# schematic.net
KiCad netlist of a schematic drawn in EasyEDA
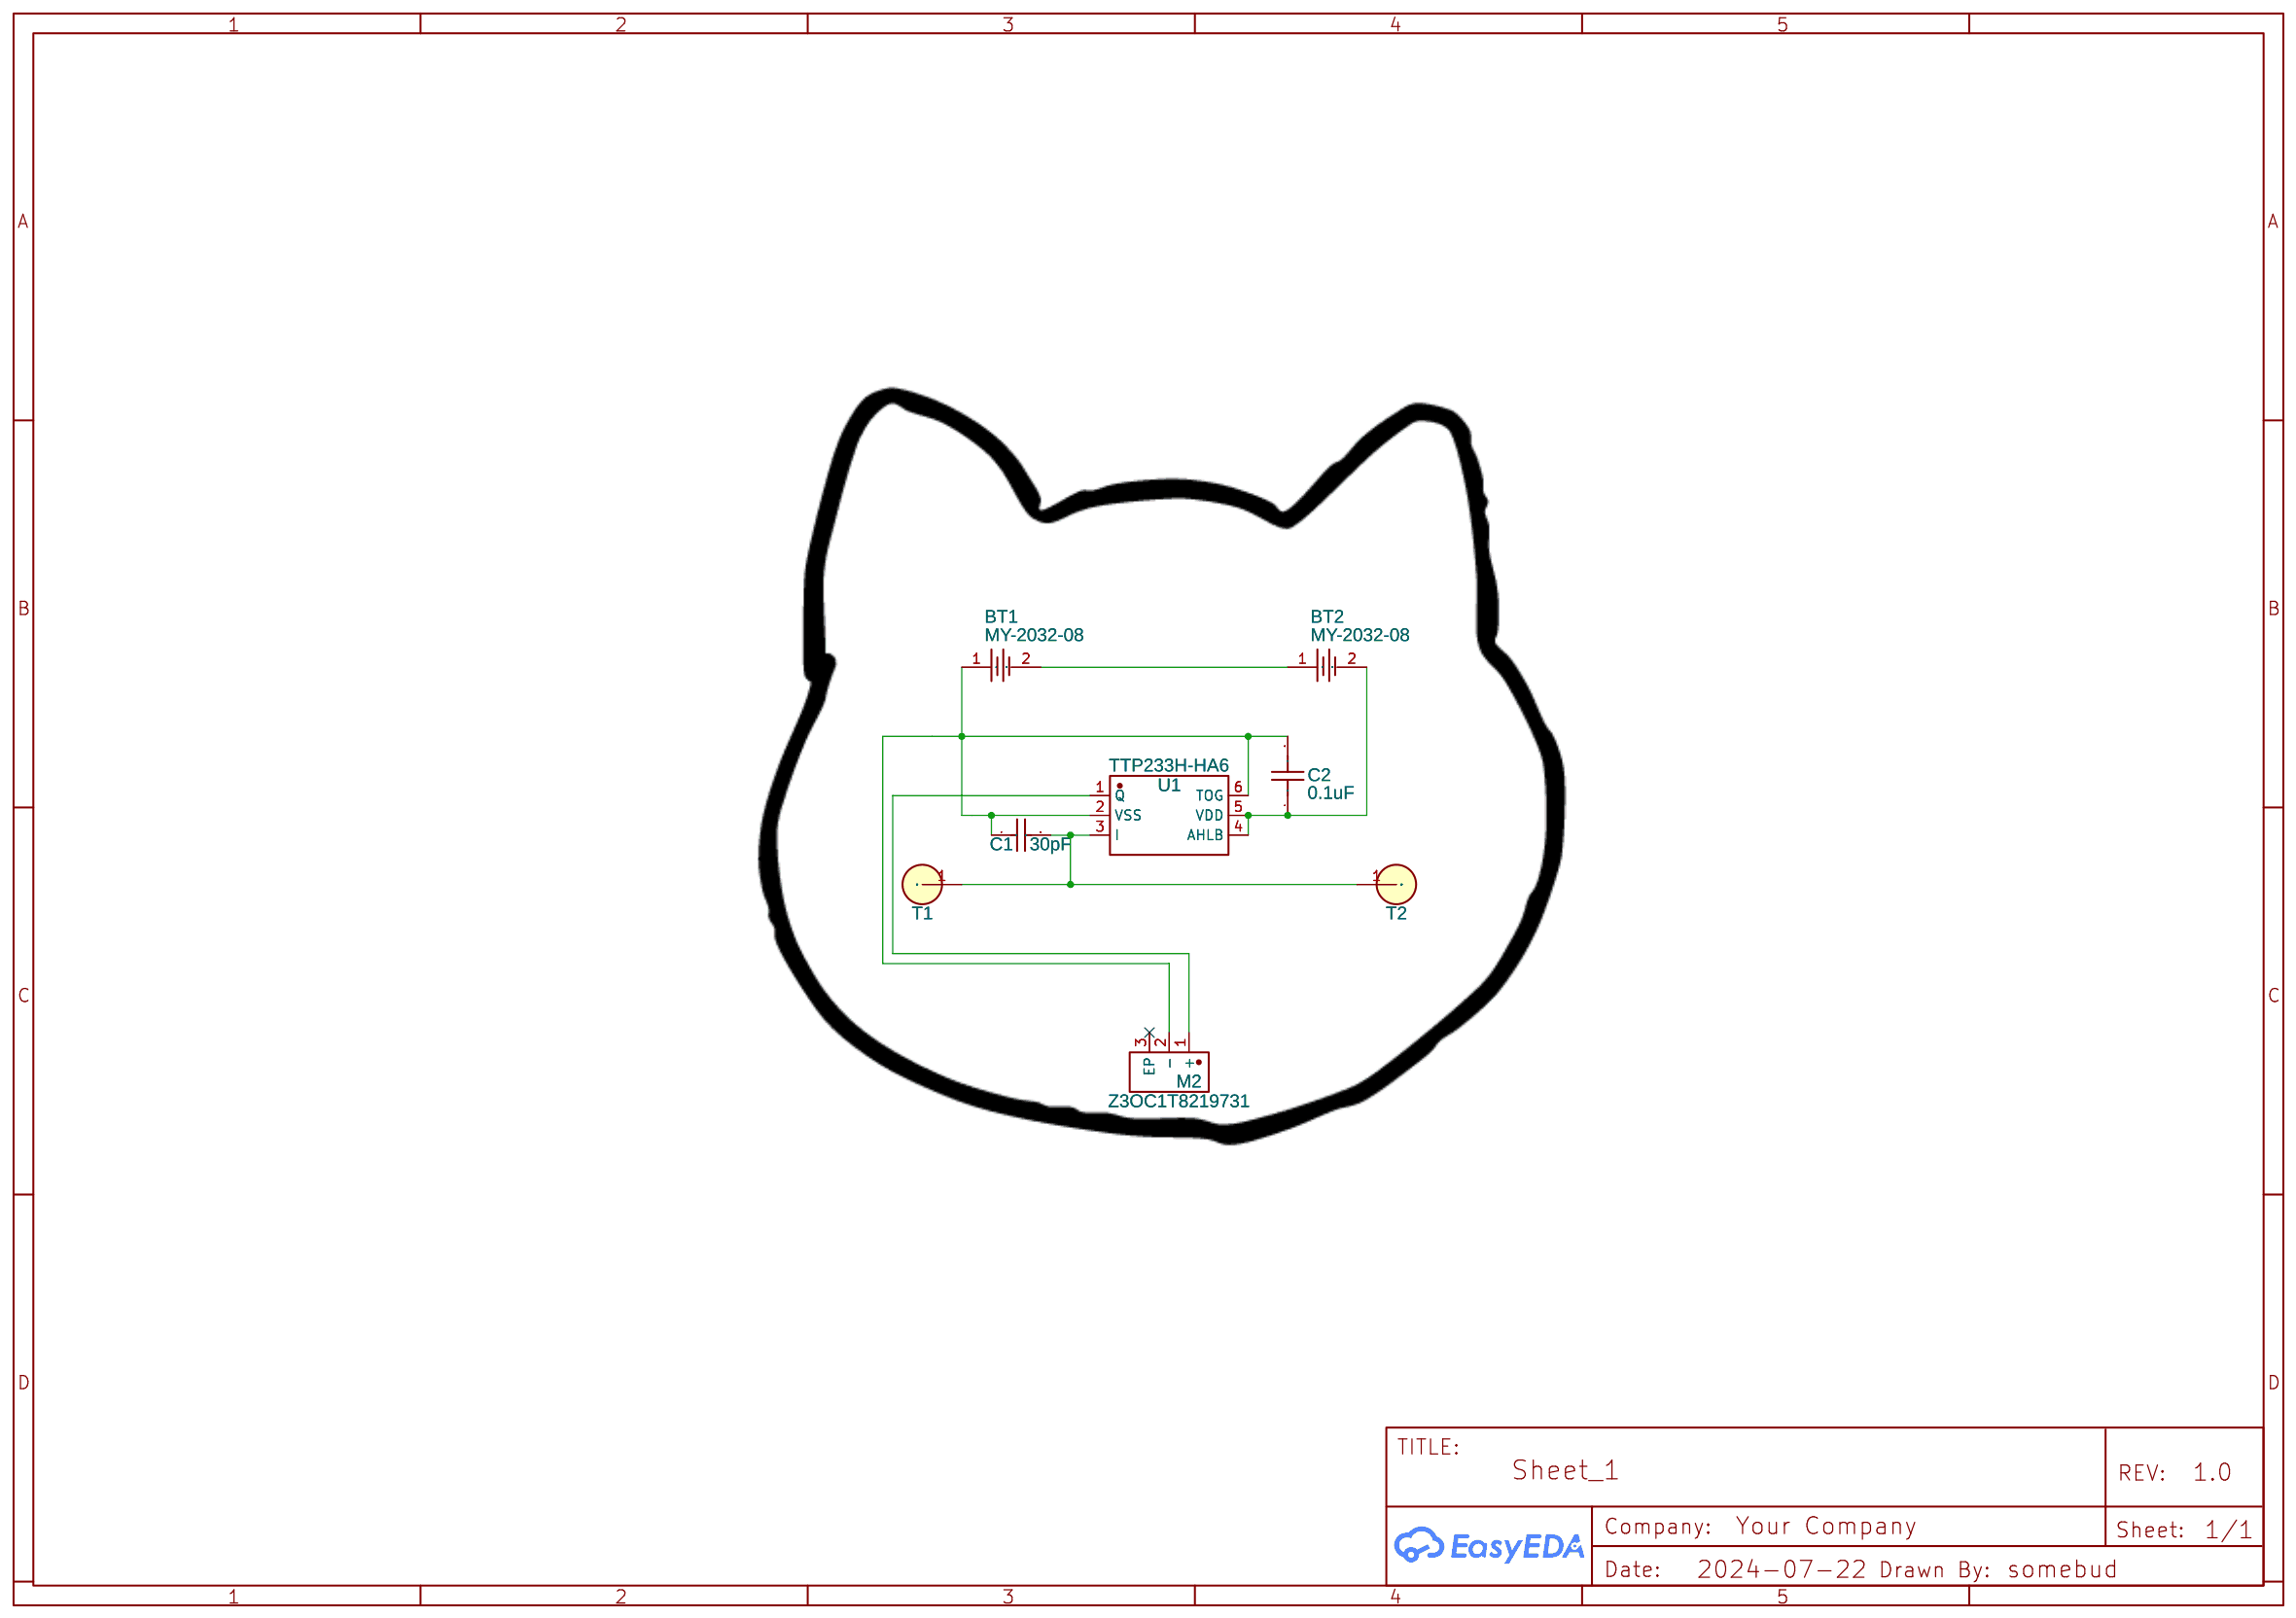
[diagram p0: schematic sheet]

(export (version "E")
  (design (tool "Eeschema 10.0.6"))
  (components
    (comp (ref "BT1")
      (value "MY-2032-08")
      (fields (field (name "Manufacturer") "MYOUNG(美阳)"))
      (libsource (lib "") (part "MY-2032-08"))
    )
    (comp (ref "BT2")
      (value "MY-2032-08")
      (fields (field (name "Manufacturer") "MYOUNG(美阳)"))
      (libsource (lib "") (part "MY-2032-08"))
    )
    (comp (ref "C1")
      (value "30pF")
      (fields (field (name "Manufacturer Part") "0603CG300J500NT") (field (name "Manufacturer") "FH(风华)"))
      (libsource (lib "") (part "0603CG300J500NT"))
    )
    (comp (ref "C2") (value "0.1uF") (libsource (lib "") (part "C_0603_US")))
    (comp (ref "M2")
      (value "Z3OC1T8219731")
      (fields (field (name "Manufacturer") "KOTL(金龙机电)"))
      (libsource (lib "") (part "Z3OC1T8219731"))
    )
    (comp (ref "T1")
      (value "TOUCHPAD 12mm circle nopaste nomask")
      (libsource (lib "") (part "TOUCHPAD 12mm circle nopaste nomask_1"))
    )
    (comp (ref "T2")
      (value "TOUCHPAD 12mm circle nopaste nomask")
      (libsource (lib "") (part "TOUCHPAD 12mm circle nopaste nomask"))
    )
    (comp (ref "U1")
      (value "TTP233H-HA6")
      (fields (field (name "Manufacturer") "TONTEK(通泰)"))
      (libsource (lib "") (part "TTP233H-HA6"))
    )
  )
  (nets
    (net (code "1") (name "Net-(BT1-Pad2)") (class "Default")
      (node (ref "BT1") (pin "2") (pinfunction "2_2") (pintype "input"))
      (node (ref "BT2") (pin "1") (pinfunction "1_1") (pintype "input"))
    )
    (net (code "2") (name "Net-(M2-+)") (class "Default")
      (node (ref "M2") (pin "1") (pinfunction "+_1") (pintype "unspecified"))
      (node (ref "U1") (pin "1") (pinfunction "Q_1") (pintype "unspecified"))
    )
    (net (code "3") (name "Net-(M2--)") (class "Default")
      (node (ref "BT1") (pin "1") (pinfunction "1_1") (pintype "input"))
      (node (ref "C1") (pin "1") (pinfunction "1_1") (pintype "input"))
      (node (ref "C2") (pin "2") (pinfunction "2_2") (pintype "unspecified"))
      (node (ref "M2") (pin "2") (pinfunction "-_2") (pintype "unspecified"))
      (node (ref "U1") (pin "2") (pinfunction "VSS_2") (pintype "unspecified"))
      (node (ref "U1") (pin "6") (pinfunction "TOG_6") (pintype "unspecified"))
    )
    (net (code "4") (name "Net-(T1-Touch)") (class "Default")
      (node (ref "C1") (pin "2") (pinfunction "2_2") (pintype "input"))
      (node (ref "T1") (pin "1") (pinfunction "Touch_1") (pintype "unspecified"))
      (node (ref "T2") (pin "1") (pinfunction "Touch_1") (pintype "unspecified"))
      (node (ref "U1") (pin "3") (pinfunction "I_3") (pintype "unspecified"))
    )
    (net (code "5") (name "Net-(U1-AHLB)") (class "Default")
      (node (ref "BT2") (pin "2") (pinfunction "2_2") (pintype "input"))
      (node (ref "C2") (pin "1") (pinfunction "1_1") (pintype "unspecified"))
      (node (ref "U1") (pin "4") (pinfunction "AHLB_4") (pintype "unspecified"))
      (node (ref "U1") (pin "5") (pinfunction "VDD_5") (pintype "unspecified"))
    )
    (net (code "6") (name "unconnected-(M2-EP-Pad3)") (class "Default")
      (node (ref "M2") (pin "3") (pinfunction "EP_3") (pintype "unspecified+no_connect"))
    )
  )
)
